# Adafruit_QT_Py_ESP32-S2_uFL.net
KiCad netlist of a schematic drawn in EAGLE
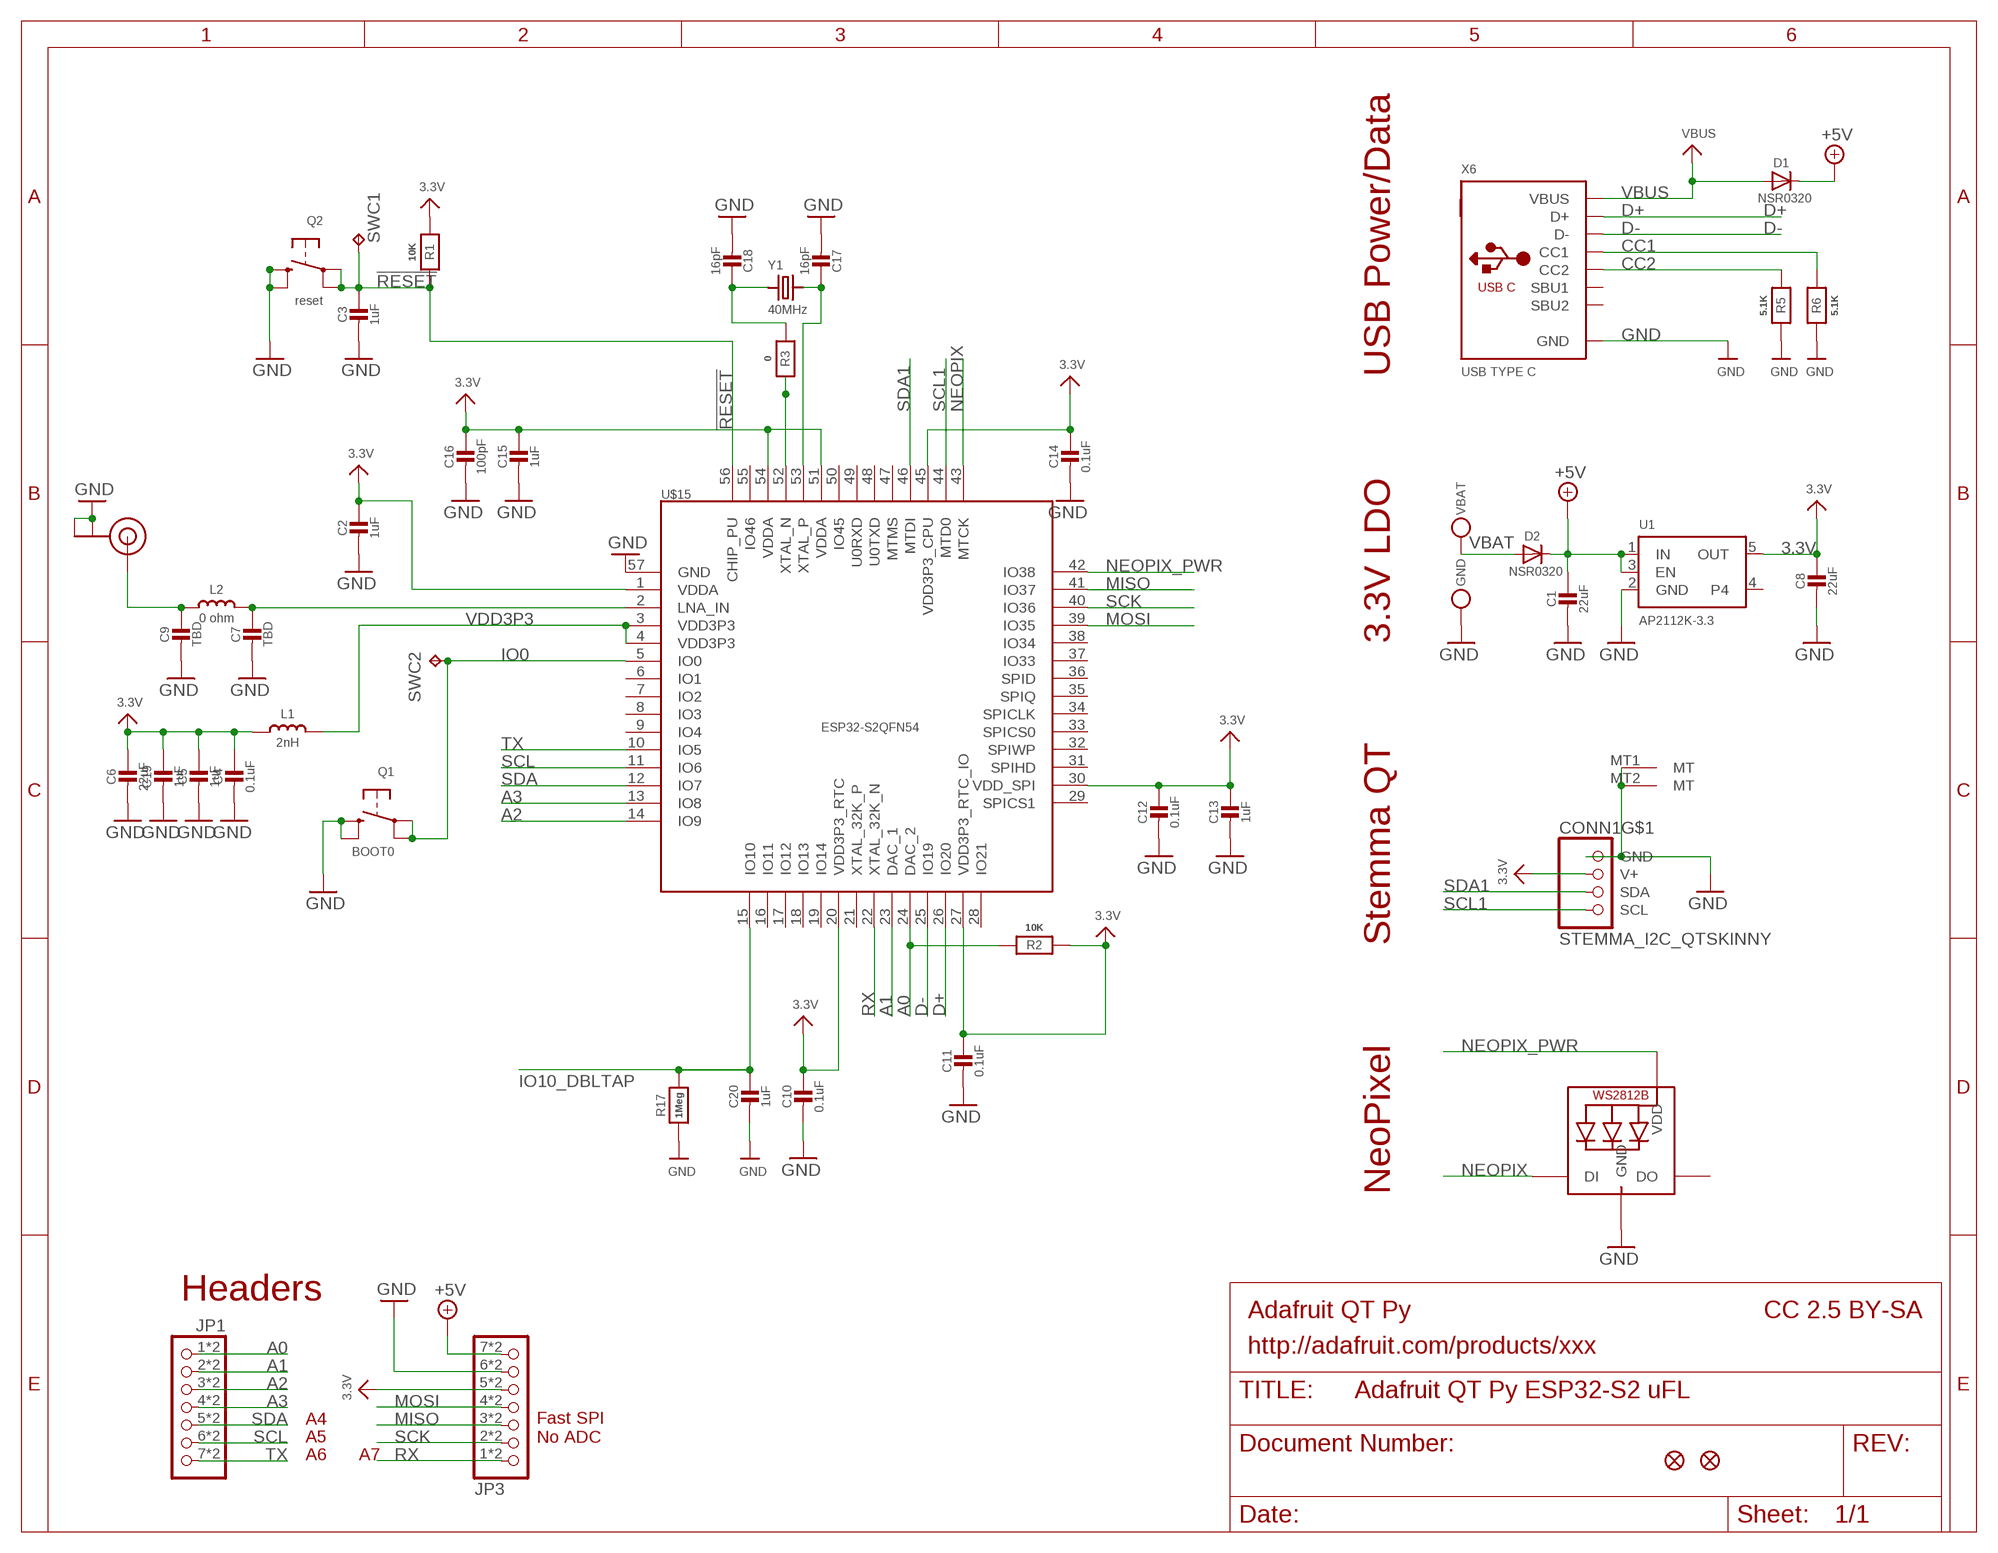
[diagram p0: schematic, sheet 1]

(export (version "E")
  (design (tool "Eeschema 10.0.6"))
  (components
    (comp (ref "C1")
      (value "22uF")
      (footprint "eagle-import:0805-NO")
      (libsource (lib "eagle-import") (part "CAP_CERAMIC0805-NOOUTLINE"))
    )
    (comp (ref "C2")
      (value "1uF")
      (footprint "eagle-import:_0402NO")
      (libsource (lib "eagle-import") (part "CAP_CERAMIC_0402NO"))
    )
    (comp (ref "C3")
      (value "1uF")
      (footprint "eagle-import:_0402NO")
      (libsource (lib "eagle-import") (part "CAP_CERAMIC_0402NO"))
    )
    (comp (ref "C4")
      (value "0.1uF")
      (footprint "eagle-import:_0402NO")
      (libsource (lib "eagle-import") (part "CAP_CERAMIC_0402NO"))
    )
    (comp (ref "C5")
      (value "1uF")
      (footprint "eagle-import:_0402NO")
      (libsource (lib "eagle-import") (part "CAP_CERAMIC_0402NO"))
    )
    (comp (ref "C6")
      (value "22uF")
      (footprint "eagle-import:0805-NO")
      (libsource (lib "eagle-import") (part "CAP_CERAMIC0805-NOOUTLINE"))
    )
    (comp (ref "C7")
      (value "TBD")
      (footprint "eagle-import:_0402NO")
      (libsource (lib "eagle-import") (part "CAP_CERAMIC_0402NO"))
    )
    (comp (ref "C8")
      (value "22uF")
      (footprint "eagle-import:0805-NO")
      (libsource (lib "eagle-import") (part "CAP_CERAMIC0805-NOOUTLINE"))
    )
    (comp (ref "C9")
      (value "TBD")
      (footprint "eagle-import:_0402NO")
      (libsource (lib "eagle-import") (part "CAP_CERAMIC_0402NO"))
    )
    (comp (ref "C10")
      (value "0.1uF")
      (footprint "eagle-import:_0402NO")
      (libsource (lib "eagle-import") (part "CAP_CERAMIC_0402NO"))
    )
    (comp (ref "C11")
      (value "0.1uF")
      (footprint "eagle-import:_0402NO")
      (libsource (lib "eagle-import") (part "CAP_CERAMIC_0402NO"))
    )
    (comp (ref "C12")
      (value "0.1uF")
      (footprint "eagle-import:_0402NO")
      (libsource (lib "eagle-import") (part "CAP_CERAMIC_0402NO"))
    )
    (comp (ref "C13")
      (value "1uF")
      (footprint "eagle-import:_0402NO")
      (libsource (lib "eagle-import") (part "CAP_CERAMIC_0402NO"))
    )
    (comp (ref "C14")
      (value "0.1uF")
      (footprint "eagle-import:_0402NO")
      (libsource (lib "eagle-import") (part "CAP_CERAMIC_0402NO"))
    )
    (comp (ref "C15")
      (value "1uF")
      (footprint "eagle-import:_0402NO")
      (libsource (lib "eagle-import") (part "CAP_CERAMIC_0402NO"))
    )
    (comp (ref "C16")
      (value "100pF")
      (footprint "eagle-import:_0402NO")
      (libsource (lib "eagle-import") (part "CAP_CERAMIC_0402NO"))
    )
    (comp (ref "C17")
      (value "16pF")
      (footprint "eagle-import:_0402NO")
      (libsource (lib "eagle-import") (part "CAP_CERAMIC_0402NO"))
    )
    (comp (ref "C18")
      (value "16pF")
      (footprint "eagle-import:_0402NO")
      (libsource (lib "eagle-import") (part "CAP_CERAMIC_0402NO"))
    )
    (comp (ref "C19")
      (value "1uF")
      (footprint "eagle-import:_0402NO")
      (libsource (lib "eagle-import") (part "CAP_CERAMIC_0402NO"))
    )
    (comp (ref "C20")
      (value "1uF")
      (footprint "eagle-import:_0402NO")
      (libsource (lib "eagle-import") (part "CAP_CERAMIC_0402NO"))
    )
    (comp (ref "CONN1")
      (value "STEMMA_I2C_QTSKINNY")
      (footprint "eagle-import:JST_SH4_SKINNY")
      (libsource (lib "eagle-import") (part "STEMMA_I2C_QTSKINNY"))
    )
    (comp (ref "D1")
      (value "NSR0320")
      (footprint "eagle-import:SOD-323_MINI")
      (libsource (lib "eagle-import") (part "DIODE_SOD323MINI"))
    )
    (comp (ref "D2")
      (value "NSR0320")
      (footprint "eagle-import:SOD-323_MINI")
      (libsource (lib "eagle-import") (part "DIODE_SOD323MINI"))
    )
    (comp (ref "GND")
      (value "TESTPOINT_1X3")
      (footprint "eagle-import:TESTPOINT_RECT_1X3MM")
      (libsource (lib "eagle-import") (part "TESTPOINT_1X3"))
    )
    (comp (ref "JP1")
      (value "HEADER-1X7_CASTEL")
      (footprint "eagle-import:1X07_CASTEL")
      (libsource (lib "eagle-import") (part "HEADER-1X7_CASTEL"))
    )
    (comp (ref "JP3")
      (value "HEADER-1X7_CASTEL")
      (footprint "eagle-import:1X07_CASTEL")
      (libsource (lib "eagle-import") (part "HEADER-1X7_CASTEL"))
    )
    (comp (ref "L1")
      (value "2nH")
      (footprint "eagle-import:_0402")
      (libsource (lib "eagle-import") (part "INDUCTOR_0402"))
    )
    (comp (ref "L2")
      (value "0 ohm")
      (footprint "eagle-import:_0402")
      (libsource (lib "eagle-import") (part "INDUCTOR_0402"))
    )
    (comp (ref "LED1")
      (value "WS2812B_SK6805_1515")
      (footprint "eagle-import:SK6805_1515")
      (libsource (lib "eagle-import") (part "WS2812B_SK6805_1515"))
    )
    (comp (ref "Q1")
      (value "BOOT0")
      (footprint "eagle-import:BTN_KMR2_4.6X2.8")
      (libsource (lib "eagle-import") (part "SWITCH_TACT_SMT4.6X2.8"))
    )
    (comp (ref "Q2")
      (value "reset")
      (footprint "eagle-import:BTN_KMR2_4.6X2.8")
      (libsource (lib "eagle-import") (part "SWITCH_TACT_SMT4.6X2.8"))
    )
    (comp (ref "R1")
      (value "10K")
      (footprint "eagle-import:_0402NO")
      (libsource (lib "eagle-import") (part "RESISTOR_0402NO"))
    )
    (comp (ref "R2")
      (value "10K")
      (footprint "eagle-import:_0402NO")
      (libsource (lib "eagle-import") (part "RESISTOR_0402NO"))
    )
    (comp (ref "R3")
      (value "0")
      (footprint "eagle-import:_0402NO")
      (libsource (lib "eagle-import") (part "RESISTOR_0402NO"))
    )
    (comp (ref "R5")
      (value "5.1K")
      (footprint "eagle-import:_0402NO")
      (libsource (lib "eagle-import") (part "RESISTOR_0402NO"))
    )
    (comp (ref "R6")
      (value "5.1K")
      (footprint "eagle-import:_0402NO")
      (libsource (lib "eagle-import") (part "RESISTOR_0402NO"))
    )
    (comp (ref "R17")
      (value "1Meg")
      (footprint "eagle-import:_0402NO")
      (libsource (lib "eagle-import") (part "RESISTOR_0402NO"))
    )
    (comp (ref "SWC1")
      (value "TPB1,27")
      (footprint "eagle-import:B1,27")
      (libsource (lib "eagle-import") (part "TPB1,27"))
    )
    (comp (ref "SWC2")
      (value "TPB1,27")
      (footprint "eagle-import:B1,27")
      (libsource (lib "eagle-import") (part "TPB1,27"))
    )
    (comp (ref "U$6")
      (value "FIDUCIAL_1MM")
      (footprint "eagle-import:FIDUCIAL_1MM")
      (libsource (lib "eagle-import") (part "FIDUCIAL_1MM"))
    )
    (comp (ref "U$8")
      (value "FIDUCIAL_1MM")
      (footprint "eagle-import:FIDUCIAL_1MM")
      (libsource (lib "eagle-import") (part "FIDUCIAL_1MM"))
    )
    (comp (ref "U$11")
      (value "U.FL")
      (footprint "eagle-import:U.FL")
      (libsource (lib "eagle-import") (part "U.FL"))
    )
    (comp (ref "U$15")
      (value "ESP32-S2QFN54")
      (footprint "eagle-import:QFN40P700X700X90-57T400N")
      (fields
        (field (name "DIGI-KEY_PART_NUMBER") "1965-ESP32-S2CT-ND")
        (field (name "MF") "Espressif Systems")
        (field (name "MP") "ESP32-S2")
      )
      (libsource (lib "eagle-import") (part "ESP32-S2QFN54"))
    )
    (comp (ref "U1")
      (value "AP2112K-3.3")
      (footprint "eagle-import:SOT23-5")
      (libsource (lib "eagle-import") (part "VREG_SOT23-5"))
    )
    (comp (ref "VBAT")
      (value "TESTPOINT_1X3")
      (footprint "eagle-import:TESTPOINT_RECT_1X3MM")
      (libsource (lib "eagle-import") (part "TESTPOINT_1X3"))
    )
    (comp (ref "X6")
      (value "USB TYPE C")
      (footprint "eagle-import:USB_C_CUSB31-CFM2AX-01-X")
      (libsource (lib "eagle-import") (part "USB_C"))
    )
    (comp (ref "Y1")
      (value "40MHz")
      (footprint "eagle-import:CRYSTAL_2X1.6")
      (libsource (lib "eagle-import") (part "CRYSTAL_2X1.6MM"))
    )
  )
  (nets
    (net (code "1") (name "+5V") (class "Default")
      (node (ref "C1") (pin "1") (pinfunction "1_1") (pintype "passive"))
      (node (ref "D1") (pin "C") (pinfunction "C_C") (pintype "passive"))
      (node (ref "D2") (pin "C") (pinfunction "C_C") (pintype "passive"))
      (node (ref "JP3") (pin "7") (pinfunction "7_7") (pintype "passive"))
      (node (ref "JP3") (pin "7C") (pinfunction "7_7C") (pintype "passive"))
      (node (ref "U1") (pin "1") (pinfunction "IN_1") (pintype "power_in"))
      (node (ref "U1") (pin "3") (pinfunction "EN_3") (pintype "input"))
    )
    (net (code "2") (name "/A0") (class "Default")
      (node (ref "JP1") (pin "1") (pinfunction "1_1") (pintype "passive"))
      (node (ref "JP1") (pin "1C") (pinfunction "1_1C") (pintype "passive"))
      (node (ref "R2") (pin "2") (pinfunction "2_2") (pintype "passive"))
      (node (ref "U$15") (pin "24") (pinfunction "DAC_2_24") (pintype "bidirectional"))
    )
    (net (code "3") (name "/A1") (class "Default")
      (node (ref "JP1") (pin "2") (pinfunction "2_2") (pintype "passive"))
      (node (ref "JP1") (pin "2C") (pinfunction "2_2C") (pintype "passive"))
      (node (ref "U$15") (pin "23") (pinfunction "DAC_1_23") (pintype "bidirectional"))
    )
    (net (code "4") (name "/A2") (class "Default")
      (node (ref "JP1") (pin "3") (pinfunction "3_3") (pintype "passive"))
      (node (ref "JP1") (pin "3C") (pinfunction "3_3C") (pintype "passive"))
      (node (ref "U$15") (pin "14") (pinfunction "IO9_14") (pintype "bidirectional"))
    )
    (net (code "5") (name "/A3") (class "Default")
      (node (ref "JP1") (pin "4") (pinfunction "4_4") (pintype "passive"))
      (node (ref "JP1") (pin "4C") (pinfunction "4_4C") (pintype "passive"))
      (node (ref "U$15") (pin "13") (pinfunction "IO8_13") (pintype "bidirectional"))
    )
    (net (code "6") (name "/CC1") (class "Default")
      (node (ref "R6") (pin "2") (pinfunction "2_2") (pintype "passive"))
      (node (ref "X6") (pin "A5") (pinfunction "CC1_A5") (pintype "bidirectional"))
    )
    (net (code "7") (name "/CC2") (class "Default")
      (node (ref "R5") (pin "2") (pinfunction "2_2") (pintype "passive"))
      (node (ref "X6") (pin "B5") (pinfunction "CC2_B5") (pintype "bidirectional"))
    )
    (net (code "8") (name "/D+") (class "Default")
      (node (ref "U$15") (pin "26") (pinfunction "IO20_26") (pintype "bidirectional"))
      (node (ref "X6") (pin "A6") (pinfunction "D+_A6") (pintype "bidirectional"))
      (node (ref "X6") (pin "B6") (pinfunction "D+_B6") (pintype "bidirectional"))
    )
    (net (code "9") (name "/D-") (class "Default")
      (node (ref "U$15") (pin "25") (pinfunction "IO19_25") (pintype "bidirectional"))
      (node (ref "X6") (pin "A7") (pinfunction "D-_A7") (pintype "bidirectional"))
      (node (ref "X6") (pin "B7") (pinfunction "D-_B7") (pintype "bidirectional"))
    )
    (net (code "10") (name "/IO0") (class "Default")
      (node (ref "Q1") (pin "A") (pinfunction "P_A") (pintype "passive"))
      (node (ref "Q1") (pin "A'") (pinfunction "P1_A'") (pintype "passive"))
      (node (ref "SWC2") (pin "TP") (pinfunction "TP_TP") (pintype "input"))
      (node (ref "U$15") (pin "5") (pinfunction "IO0_5") (pintype "bidirectional"))
    )
    (net (code "11") (name "/IO10_DBLTAP") (class "Default")
      (node (ref "C20") (pin "1") (pinfunction "1_1") (pintype "passive"))
      (node (ref "R17") (pin "2") (pinfunction "2_2") (pintype "passive"))
      (node (ref "U$15") (pin "15") (pinfunction "IO10_15") (pintype "bidirectional"))
    )
    (net (code "12") (name "/MISO") (class "Default")
      (node (ref "JP3") (pin "3") (pinfunction "3_3") (pintype "passive"))
      (node (ref "JP3") (pin "3C") (pinfunction "3_3C") (pintype "passive"))
      (node (ref "U$15") (pin "41") (pinfunction "IO37_41") (pintype "bidirectional"))
    )
    (net (code "13") (name "/MOSI") (class "Default")
      (node (ref "JP3") (pin "4") (pinfunction "4_4") (pintype "passive"))
      (node (ref "JP3") (pin "4C") (pinfunction "4_4C") (pintype "passive"))
      (node (ref "U$15") (pin "39") (pinfunction "IO35_39") (pintype "bidirectional"))
    )
    (net (code "14") (name "/NEOPIX") (class "Default")
      (node (ref "LED1") (pin "1") (pinfunction "DI_1") (pintype "input"))
      (node (ref "U$15") (pin "43") (pinfunction "MTCK_43") (pintype "bidirectional"))
    )
    (net (code "15") (name "/NEOPIX_PWR") (class "Default")
      (node (ref "LED1") (pin "2") (pinfunction "VDD_2") (pintype "power_in"))
      (node (ref "U$15") (pin "42") (pinfunction "IO38_42") (pintype "bidirectional"))
    )
    (net (code "16") (name "/RX") (class "Default")
      (node (ref "JP3") (pin "1") (pinfunction "1_1") (pintype "passive"))
      (node (ref "JP3") (pin "1C") (pinfunction "1_1C") (pintype "passive"))
      (node (ref "U$15") (pin "22") (pinfunction "XTAL_32K_N_22") (pintype "bidirectional"))
    )
    (net (code "17") (name "/SCK") (class "Default")
      (node (ref "JP3") (pin "2") (pinfunction "2_2") (pintype "passive"))
      (node (ref "JP3") (pin "2C") (pinfunction "2_2C") (pintype "passive"))
      (node (ref "U$15") (pin "40") (pinfunction "IO36_40") (pintype "bidirectional"))
    )
    (net (code "18") (name "/SCL") (class "Default")
      (node (ref "JP1") (pin "6") (pinfunction "6_6") (pintype "passive"))
      (node (ref "JP1") (pin "6C") (pinfunction "6_6C") (pintype "passive"))
      (node (ref "U$15") (pin "11") (pinfunction "IO6_11") (pintype "bidirectional"))
    )
    (net (code "19") (name "/SCL1") (class "Default")
      (node (ref "CONN1") (pin "4") (pinfunction "SCL_4") (pintype "passive"))
      (node (ref "U$15") (pin "44") (pinfunction "MTD0_44") (pintype "bidirectional"))
    )
    (net (code "20") (name "/SDA") (class "Default")
      (node (ref "JP1") (pin "5") (pinfunction "5_5") (pintype "passive"))
      (node (ref "JP1") (pin "5C") (pinfunction "5_5C") (pintype "passive"))
      (node (ref "U$15") (pin "12") (pinfunction "IO7_12") (pintype "bidirectional"))
    )
    (net (code "21") (name "/SDA1") (class "Default")
      (node (ref "CONN1") (pin "3") (pinfunction "SDA_3") (pintype "passive"))
      (node (ref "U$15") (pin "46") (pinfunction "MTDI_46") (pintype "bidirectional"))
    )
    (net (code "22") (name "/TX") (class "Default")
      (node (ref "JP1") (pin "7") (pinfunction "7_7") (pintype "passive"))
      (node (ref "JP1") (pin "7C") (pinfunction "7_7C") (pintype "passive"))
      (node (ref "U$15") (pin "10") (pinfunction "IO5_10") (pintype "bidirectional"))
    )
    (net (code "23") (name "/VBAT") (class "Default")
      (node (ref "D2") (pin "A") (pinfunction "A_A") (pintype "passive"))
      (node (ref "VBAT") (pin "P$1") (pinfunction "P$1_P$1") (pintype "bidirectional"))
    )
    (net (code "24") (name "/VDD3P3") (class "Default")
      (node (ref "L1") (pin "2") (pinfunction "2_2") (pintype "passive"))
      (node (ref "U$15") (pin "3") (pinfunction "VDD3P3_3") (pintype "power_in"))
      (node (ref "U$15") (pin "4") (pinfunction "VDD3P3_4") (pintype "power_in"))
    )
    (net (code "25") (name "/~{RESET}") (class "Default")
      (node (ref "C3") (pin "1") (pinfunction "1_1") (pintype "passive"))
      (node (ref "Q2") (pin "A") (pinfunction "P_A") (pintype "passive"))
      (node (ref "Q2") (pin "A'") (pinfunction "P1_A'") (pintype "passive"))
      (node (ref "R1") (pin "2") (pinfunction "2_2") (pintype "passive"))
      (node (ref "SWC1") (pin "TP") (pinfunction "TP_TP") (pintype "input"))
      (node (ref "U$15") (pin "56") (pinfunction "CHIP_PU_56") (pintype "input"))
    )
    (net (code "26") (name "3.3V") (class "Default")
      (node (ref "C10") (pin "1") (pinfunction "1_1") (pintype "passive"))
      (node (ref "C11") (pin "1") (pinfunction "1_1") (pintype "passive"))
      (node (ref "C12") (pin "1") (pinfunction "1_1") (pintype "passive"))
      (node (ref "C13") (pin "1") (pinfunction "1_1") (pintype "passive"))
      (node (ref "C14") (pin "1") (pinfunction "1_1") (pintype "passive"))
      (node (ref "C15") (pin "1") (pinfunction "1_1") (pintype "passive"))
      (node (ref "C16") (pin "1") (pinfunction "1_1") (pintype "passive"))
      (node (ref "C19") (pin "1") (pinfunction "1_1") (pintype "passive"))
      (node (ref "C2") (pin "1") (pinfunction "1_1") (pintype "passive"))
      (node (ref "C4") (pin "1") (pinfunction "1_1") (pintype "passive"))
      (node (ref "C5") (pin "1") (pinfunction "1_1") (pintype "passive"))
      (node (ref "C6") (pin "1") (pinfunction "1_1") (pintype "passive"))
      (node (ref "C8") (pin "1") (pinfunction "1_1") (pintype "passive"))
      (node (ref "CONN1") (pin "2") (pinfunction "V+_2") (pintype "passive"))
      (node (ref "JP3") (pin "5") (pinfunction "5_5") (pintype "passive"))
      (node (ref "JP3") (pin "5C") (pinfunction "5_5C") (pintype "passive"))
      (node (ref "L1") (pin "1") (pinfunction "1_1") (pintype "passive"))
      (node (ref "R1") (pin "1") (pinfunction "1_1") (pintype "passive"))
      (node (ref "R2") (pin "1") (pinfunction "1_1") (pintype "passive"))
      (node (ref "U$15") (pin "1") (pinfunction "VDDA_1") (pintype "power_in"))
      (node (ref "U$15") (pin "20") (pinfunction "VDD3P3_RTC_20") (pintype "power_in"))
      (node (ref "U$15") (pin "27") (pinfunction "VDD3P3_RTC_IO_27") (pintype "power_in"))
      (node (ref "U$15") (pin "30") (pinfunction "VDD_SPI_30") (pintype "power_in"))
      (node (ref "U$15") (pin "45") (pinfunction "VDD3P3_CPU_45") (pintype "power_in"))
      (node (ref "U$15") (pin "51") (pinfunction "VDDA_51") (pintype "power_in"))
      (node (ref "U$15") (pin "54") (pinfunction "VDDA_54") (pintype "power_in"))
      (node (ref "U1") (pin "5") (pinfunction "OUT_5") (pintype "power_in"))
    )
    (net (code "27") (name "GND") (class "Default")
      (node (ref "C1") (pin "2") (pinfunction "2_2") (pintype "passive"))
      (node (ref "C10") (pin "2") (pinfunction "2_2") (pintype "passive"))
      (node (ref "C11") (pin "2") (pinfunction "2_2") (pintype "passive"))
      (node (ref "C12") (pin "2") (pinfunction "2_2") (pintype "passive"))
      (node (ref "C13") (pin "2") (pinfunction "2_2") (pintype "passive"))
      (node (ref "C14") (pin "2") (pinfunction "2_2") (pintype "passive"))
      (node (ref "C15") (pin "2") (pinfunction "2_2") (pintype "passive"))
      (node (ref "C16") (pin "2") (pinfunction "2_2") (pintype "passive"))
      (node (ref "C17") (pin "2") (pinfunction "2_2") (pintype "passive"))
      (node (ref "C18") (pin "2") (pinfunction "2_2") (pintype "passive"))
      (node (ref "C19") (pin "2") (pinfunction "2_2") (pintype "passive"))
      (node (ref "C2") (pin "2") (pinfunction "2_2") (pintype "passive"))
      (node (ref "C20") (pin "2") (pinfunction "2_2") (pintype "passive"))
      (node (ref "C3") (pin "2") (pinfunction "2_2") (pintype "passive"))
      (node (ref "C4") (pin "2") (pinfunction "2_2") (pintype "passive"))
      (node (ref "C5") (pin "2") (pinfunction "2_2") (pintype "passive"))
      (node (ref "C6") (pin "2") (pinfunction "2_2") (pintype "passive"))
      (node (ref "C7") (pin "2") (pinfunction "2_2") (pintype "passive"))
      (node (ref "C8") (pin "2") (pinfunction "2_2") (pintype "passive"))
      (node (ref "C9") (pin "2") (pinfunction "2_2") (pintype "passive"))
      (node (ref "CONN1") (pin "1") (pinfunction "GND_1") (pintype "passive"))
      (node (ref "CONN1") (pin "MT1") (pinfunction "MT_MT1") (pintype "bidirectional"))
      (node (ref "CONN1") (pin "MT2") (pinfunction "MT_MT2") (pintype "bidirectional"))
      (node (ref "GND") (pin "P$1") (pinfunction "P$1_P$1") (pintype "bidirectional"))
      (node (ref "JP3") (pin "6") (pinfunction "6_6") (pintype "passive"))
      (node (ref "JP3") (pin "6C") (pinfunction "6_6C") (pintype "passive"))
      (node (ref "LED1") (pin "4") (pinfunction "GND_4") (pintype "power_in"))
      (node (ref "Q1") (pin "B") (pinfunction "S_B") (pintype "passive"))
      (node (ref "Q1") (pin "B'") (pinfunction "S1_B'") (pintype "passive"))
      (node (ref "Q2") (pin "B") (pinfunction "S_B") (pintype "passive"))
      (node (ref "Q2") (pin "B'") (pinfunction "S1_B'") (pintype "passive"))
      (node (ref "R17") (pin "1") (pinfunction "1_1") (pintype "passive"))
      (node (ref "R5") (pin "1") (pinfunction "1_1") (pintype "passive"))
      (node (ref "R6") (pin "1") (pinfunction "1_1") (pintype "passive"))
      (node (ref "U$11") (pin "P$1") (pinfunction "GND_P$1") (pintype "bidirectional"))
      (node (ref "U$11") (pin "P$2") (pinfunction "GND_P$2") (pintype "bidirectional"))
      (node (ref "U$15") (pin "57") (pinfunction "GND_57") (pintype "power_in"))
      (node (ref "U1") (pin "2") (pinfunction "GND_2") (pintype "power_in"))
      (node (ref "X6") (pin "A1B12") (pinfunction "GND_A1B12") (pintype "power_in"))
      (node (ref "X6") (pin "B1A12") (pinfunction "GND_B1A12") (pintype "power_in"))
    )
    (net (code "28") (name "Net-(C18-Pad1)") (class "Default")
      (node (ref "C18") (pin "1") (pinfunction "1_1") (pintype "passive"))
      (node (ref "R3") (pin "1") (pinfunction "1_1") (pintype "passive"))
      (node (ref "Y1") (pin "1") (pinfunction "1_1") (pintype "passive"))
    )
    (net (code "29") (name "Net-(U$11-SIGNAL)") (class "Default")
      (node (ref "C9") (pin "1") (pinfunction "1_1") (pintype "passive"))
      (node (ref "L2") (pin "1") (pinfunction "1_1") (pintype "passive"))
      (node (ref "U$11") (pin "P$3") (pinfunction "SIGNAL_P$3") (pintype "bidirectional"))
    )
    (net (code "30") (name "Net-(U$15-LNA_IN)") (class "Default")
      (node (ref "C7") (pin "1") (pinfunction "1_1") (pintype "passive"))
      (node (ref "L2") (pin "2") (pinfunction "2_2") (pintype "passive"))
      (node (ref "U$15") (pin "2") (pinfunction "LNA_IN_2") (pintype "bidirectional"))
    )
    (net (code "31") (name "Net-(U$15-XTAL_N)") (class "Default")
      (node (ref "R3") (pin "2") (pinfunction "2_2") (pintype "passive"))
      (node (ref "U$15") (pin "52") (pinfunction "XTAL_N_52") (pintype "bidirectional"))
    )
    (net (code "32") (name "Net-(U$15-XTAL_P)") (class "Default")
      (node (ref "C17") (pin "1") (pinfunction "1_1") (pintype "passive"))
      (node (ref "U$15") (pin "53") (pinfunction "XTAL_P_53") (pintype "bidirectional"))
      (node (ref "Y1") (pin "3") (pinfunction "2_3") (pintype "passive"))
    )
    (net (code "33") (name "VBUS") (class "Default")
      (node (ref "D1") (pin "A") (pinfunction "A_A") (pintype "passive"))
      (node (ref "X6") (pin "A4B9") (pinfunction "VBUS_A4B9") (pintype "power_in"))
      (node (ref "X6") (pin "B4A9") (pinfunction "VBUS_B4A9") (pintype "power_in"))
    )
    (net (code "34") (name "unconnected-(LED1-DO-Pad3)") (class "Default")
      (node (ref "LED1") (pin "3") (pinfunction "DO_3") (pintype "output"))
    )
    (net (code "35") (name "unconnected-(U$15-IO1-Pad6)") (class "Default")
      (node (ref "U$15") (pin "6") (pinfunction "IO1_6") (pintype "bidirectional"))
    )
    (net (code "36") (name "unconnected-(U$15-IO2-Pad7)") (class "Default")
      (node (ref "U$15") (pin "7") (pinfunction "IO2_7") (pintype "bidirectional"))
    )
    (net (code "37") (name "unconnected-(U$15-IO3-Pad8)") (class "Default")
      (node (ref "U$15") (pin "8") (pinfunction "IO3_8") (pintype "bidirectional"))
    )
    (net (code "38") (name "unconnected-(U$15-IO4-Pad9)") (class "Default")
      (node (ref "U$15") (pin "9") (pinfunction "IO4_9") (pintype "bidirectional"))
    )
    (net (code "39") (name "unconnected-(U$15-IO11-Pad16)") (class "Default")
      (node (ref "U$15") (pin "16") (pinfunction "IO11_16") (pintype "bidirectional"))
    )
    (net (code "40") (name "unconnected-(U$15-IO12-Pad17)") (class "Default")
      (node (ref "U$15") (pin "17") (pinfunction "IO12_17") (pintype "bidirectional"))
    )
    (net (code "41") (name "unconnected-(U$15-IO13-Pad18)") (class "Default")
      (node (ref "U$15") (pin "18") (pinfunction "IO13_18") (pintype "bidirectional"))
    )
    (net (code "42") (name "unconnected-(U$15-IO14-Pad19)") (class "Default")
      (node (ref "U$15") (pin "19") (pinfunction "IO14_19") (pintype "bidirectional"))
    )
    (net (code "43") (name "unconnected-(U$15-IO21-Pad28)") (class "Default")
      (node (ref "U$15") (pin "28") (pinfunction "IO21_28") (pintype "bidirectional"))
    )
    (net (code "44") (name "unconnected-(U$15-IO33-Pad37)") (class "Default")
      (node (ref "U$15") (pin "37") (pinfunction "IO33_37") (pintype "bidirectional"))
    )
    (net (code "45") (name "unconnected-(U$15-IO34-Pad38)") (class "Default")
      (node (ref "U$15") (pin "38") (pinfunction "IO34_38") (pintype "bidirectional"))
    )
    (net (code "46") (name "unconnected-(U$15-IO45-Pad50)") (class "Default")
      (node (ref "U$15") (pin "50") (pinfunction "IO45_50") (pintype "bidirectional"))
    )
    (net (code "47") (name "unconnected-(U$15-IO46-Pad55)") (class "Default")
      (node (ref "U$15") (pin "55") (pinfunction "IO46_55") (pintype "input"))
    )
    (net (code "48") (name "unconnected-(U$15-MTMS-Pad47)") (class "Default")
      (node (ref "U$15") (pin "47") (pinfunction "MTMS_47") (pintype "bidirectional"))
    )
    (net (code "49") (name "unconnected-(U$15-SPICLK-Pad34)") (class "Default")
      (node (ref "U$15") (pin "34") (pinfunction "SPICLK_34") (pintype "bidirectional"))
    )
    (net (code "50") (name "unconnected-(U$15-SPICS0-Pad33)") (class "Default")
      (node (ref "U$15") (pin "33") (pinfunction "SPICS0_33") (pintype "bidirectional"))
    )
    (net (code "51") (name "unconnected-(U$15-SPICS1-Pad29)") (class "Default")
      (node (ref "U$15") (pin "29") (pinfunction "SPICS1_29") (pintype "bidirectional"))
    )
    (net (code "52") (name "unconnected-(U$15-SPID-Pad36)") (class "Default")
      (node (ref "U$15") (pin "36") (pinfunction "SPID_36") (pintype "bidirectional"))
    )
    (net (code "53") (name "unconnected-(U$15-SPIHD-Pad31)") (class "Default")
      (node (ref "U$15") (pin "31") (pinfunction "SPIHD_31") (pintype "bidirectional"))
    )
    (net (code "54") (name "unconnected-(U$15-SPIQ-Pad35)") (class "Default")
      (node (ref "U$15") (pin "35") (pinfunction "SPIQ_35") (pintype "bidirectional"))
    )
    (net (code "55") (name "unconnected-(U$15-SPIWP-Pad32)") (class "Default")
      (node (ref "U$15") (pin "32") (pinfunction "SPIWP_32") (pintype "bidirectional"))
    )
    (net (code "56") (name "unconnected-(U$15-U0RXD-Pad49)") (class "Default")
      (node (ref "U$15") (pin "49") (pinfunction "U0RXD_49") (pintype "bidirectional"))
    )
    (net (code "57") (name "unconnected-(U$15-U0TXD-Pad48)") (class "Default")
      (node (ref "U$15") (pin "48") (pinfunction "U0TXD_48") (pintype "bidirectional"))
    )
    (net (code "58") (name "unconnected-(U$15-XTAL_32K_P-Pad21)") (class "Default")
      (node (ref "U$15") (pin "21") (pinfunction "XTAL_32K_P_21") (pintype "bidirectional"))
    )
    (net (code "59") (name "unconnected-(U1-P4-Pad4)") (class "Default")
      (node (ref "U1") (pin "4") (pinfunction "P4_4") (pintype "bidirectional"))
    )
    (net (code "60") (name "unconnected-(X6-SBU1-PadA8)") (class "Default")
      (node (ref "X6") (pin "A8") (pinfunction "SBU1_A8") (pintype "bidirectional"))
    )
    (net (code "61") (name "unconnected-(X6-SBU2-PadB8)") (class "Default")
      (node (ref "X6") (pin "B8") (pinfunction "SBU2_B8") (pintype "bidirectional"))
    )
  )
)
